# project_team_result.net
KiCad netlist of a schematic drawn in Altium Designer
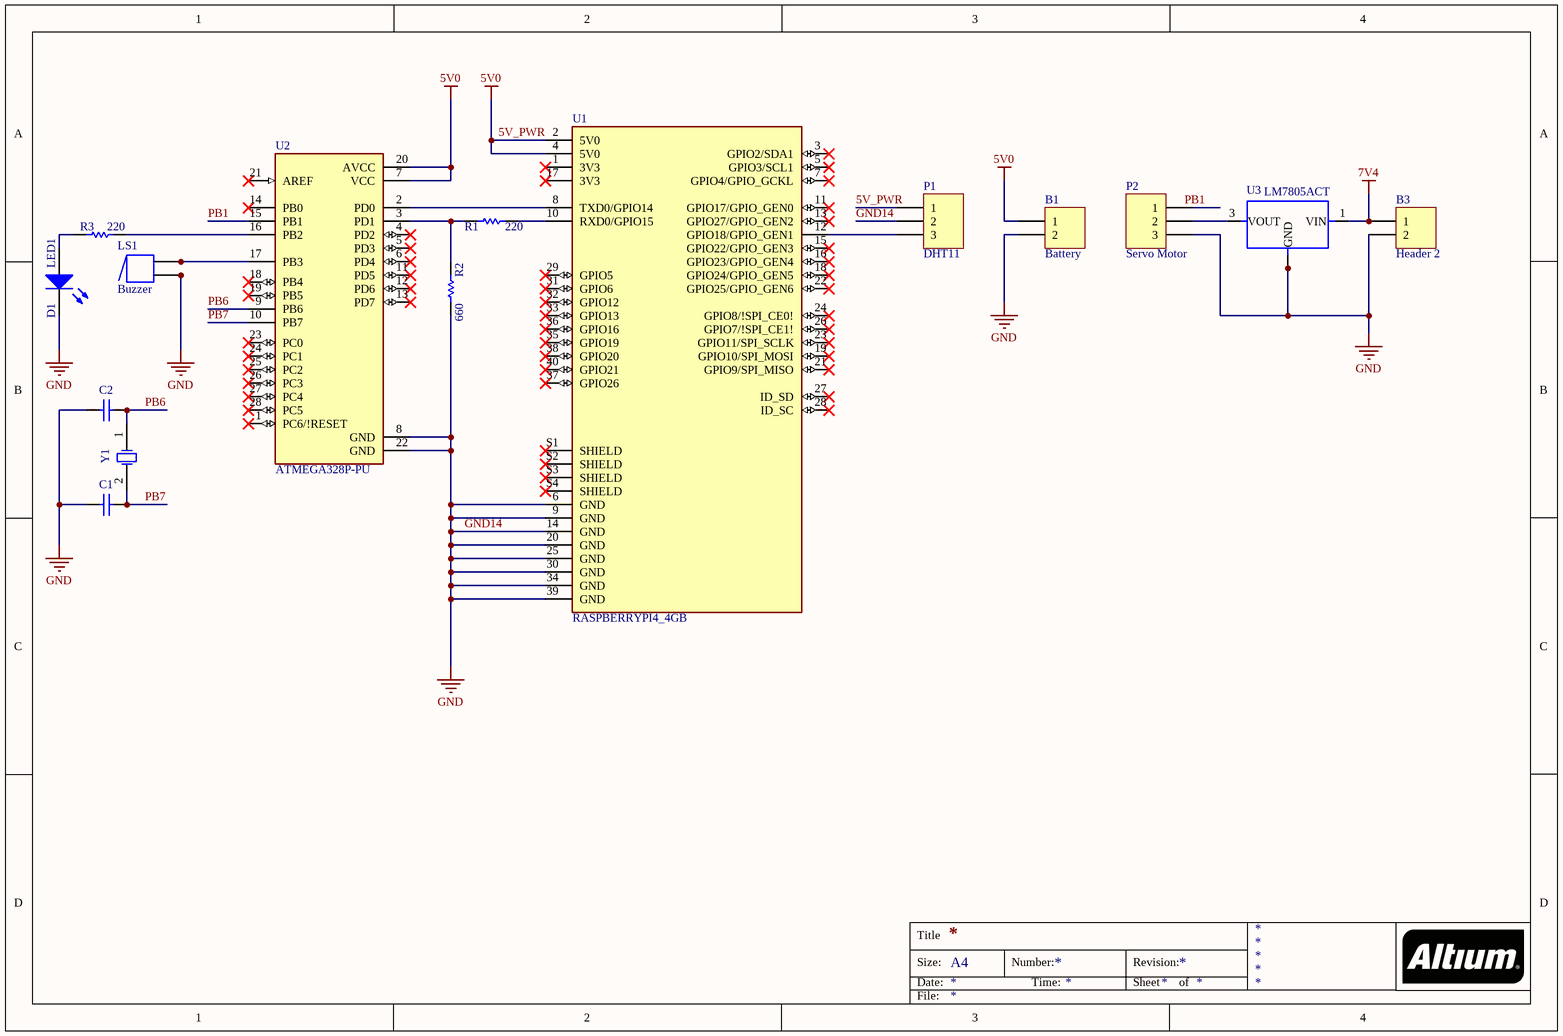
[diagram p0: project_team_result.SchDoc]

(export (version "E")
  (design (tool "Eeschema 10.0.6"))
  (components
    (comp (ref "B1")
      (value "Battery")
      (footprint "HDR1X2")
      (description "Header, 2-Pin")
      (fields (field (name "PUBLISHER") "Altium Limited"))
      (libsource (lib "Miscellaneous Connectors") (part "Header 2"))
    )
    (comp (ref "B3")
      (value "Header 2")
      (footprint "HDR1X2")
      (description "Header, 2-Pin")
      (fields (field (name "PUBLISHER") "Altium Limited"))
      (libsource (lib "Miscellaneous Connectors") (part "Header 2"))
    )
    (comp (ref "C1")
      (value "Cap")
      (footprint "RAD-0.3")
      (description "Capacitor")
      (fields (field (name "PUBLISHER") "Altium Limited"))
      (libsource (lib "Miscellaneous Devices") (part "Cap"))
    )
    (comp (ref "C2")
      (value "Cap")
      (footprint "RAD-0.3")
      (description "Capacitor")
      (fields (field (name "PUBLISHER") "Altium Limited"))
      (libsource (lib "Miscellaneous Devices") (part "Cap"))
    )
    (comp (ref "D1")
      (value "LED1")
      (footprint "LED-1")
      (description "Typical RED GaAs LED")
      (fields (field (name "PUBLISHER") "Altium Limited"))
      (libsource (lib "Miscellaneous Devices") (part "LED1"))
    )
    (comp (ref "LS1")
      (value "Buzzer")
      (footprint "ABSM-1574")
      (description "Magnetic Transducer Buzzer")
      (fields (field (name "PUBLISHER") "Altium Limited"))
      (libsource (lib "Miscellaneous Devices") (part "Buzzer"))
    )
    (comp (ref "P1")
      (value "DHT11")
      (footprint "HDR1X3")
      (description "Header, 3-Pin")
      (fields (field (name "PUBLISHER") "Altium Limited"))
      (libsource (lib "") (part "Header 3_1"))
    )
    (comp (ref "P2")
      (value "Servo Motor")
      (footprint "HDR1X3")
      (description "Header, 3-Pin")
      (fields (field (name "PUBLISHER") "Altium Limited"))
      (libsource (lib "Miscellaneous Connectors") (part "Header 3"))
    )
    (comp (ref "R1")
      (value "220")
      (footprint "AXIAL-0.3")
      (description "Resistor")
      (fields (field (name "Comment") "Res1") (field (name "PUBLISHER") "Altium Limited"))
      (libsource (lib "Miscellaneous Devices") (part "Res1"))
    )
    (comp (ref "R2")
      (value "660")
      (footprint "AXIAL-0.3")
      (description "Resistor")
      (fields (field (name "Comment") "Res1") (field (name "PUBLISHER") "Altium Limited"))
      (libsource (lib "Miscellaneous Devices") (part "Res1"))
    )
    (comp (ref "R3")
      (value "220")
      (footprint "AXIAL-0.3")
      (description "Resistor")
      (fields (field (name "Comment") "Res1") (field (name "PUBLISHER") "Altium Limited"))
      (libsource (lib "Miscellaneous Devices") (part "Res1"))
    )
    (comp (ref "U1")
      (value "RASPBERRYPI4_4GB")
      (footprint "MODULE_RASPBERRYPI4_4GB:MODULE_RASPBERRYPI4_4GB")
      (description "BCM2711 Raspberry Pi 4 Model B 4GB - ARMÂ® CortexÂ®-A72 MPU Embedded Evaluation Board")
      (fields (field (name "MF") "Raspberry Pi Foundation (NF)") (field (name "MP") "RASPBERRYPI4 4GB"))
      (libsource (lib "RASPBERRYPI4_4GB") (part "RASPBERRYPI4_4GB"))
    )
    (comp (ref "U2")
      (value "ATMEGA328P-PU")
      (footprint "SnapEDApcb:DIP794W46P254L2967H457Q28B")
      (description "AVR AVRÂ® ATmega Microcontroller IC 8-Bit 20MHz 32KB _16K x 16_ FLASH 28-PDIP")
      (fields (field (name "MF") "Microchip"))
      (libsource (lib "ATMEGA328P-PU") (part "ATMEGA328P-PU"))
    )
    (comp (ref "U3")
      (value "LM7805ACT")
      (footprint "TO-220")
      (description "Linear Voltage Regulator IC 1 Output 1A TO-220-3")
      (fields (field (name "MF") "ON Semiconductor"))
      (libsource (lib "PMIC-LM7805ACT_TO-220_") (part "PMIC-LM7805ACT(TO-220)"))
    )
    (comp (ref "Y1")
      (value "XTAL")
      (footprint "R38")
      (description "Crystal Oscillator")
      (fields (field (name "PUBLISHER") "Altium Limited"))
      (libsource (lib "Miscellaneous Devices") (part "XTAL"))
    )
  )
  (nets
    (net (code "1") (name "/PB1") (class "Default")
      (node (ref "P2") (pin "1") (pinfunction "1_1") (pintype "passive"))
      (node (ref "U2") (pin "15") (pinfunction "PB1_15") (pintype "passive"))
    )
    (net (code "2") (name "/PB6") (class "Default")
      (node (ref "C2") (pin "2") (pinfunction "2_2") (pintype "passive"))
      (node (ref "U2") (pin "9") (pinfunction "PB6_9") (pintype "passive"))
      (node (ref "Y1") (pin "1") (pinfunction "OSC1_1") (pintype "passive"))
    )
    (net (code "3") (name "/PB7") (class "Default")
      (node (ref "C1") (pin "1") (pinfunction "1_1") (pintype "passive"))
      (node (ref "U2") (pin "10") (pinfunction "PB7_10") (pintype "passive"))
      (node (ref "Y1") (pin "2") (pinfunction "OSC2_2") (pintype "passive"))
    )
    (net (code "4") (name "5V0") (class "Default")
      (node (ref "B1") (pin "1") (pinfunction "1_1") (pintype "passive"))
      (node (ref "P1") (pin "1") (pinfunction "1_1") (pintype "passive"))
      (node (ref "U1") (pin "2") (pinfunction "5V0_2") (pintype "power_in"))
      (node (ref "U1") (pin "4") (pinfunction "5V0_4") (pintype "power_in"))
      (node (ref "U2") (pin "20") (pinfunction "AVCC_20") (pintype "power_in"))
      (node (ref "U2") (pin "7") (pinfunction "VCC_7") (pintype "power_in"))
    )
    (net (code "5") (name "7V4") (class "Default")
      (node (ref "B3") (pin "1") (pinfunction "1_1") (pintype "passive"))
      (node (ref "U3") (pin "1") (pinfunction "VIN_1") (pintype "passive"))
    )
    (net (code "6") (name "GND") (class "Default")
      (node (ref "B1") (pin "2") (pinfunction "2_2") (pintype "passive"))
      (node (ref "B3") (pin "2") (pinfunction "2_2") (pintype "passive"))
      (node (ref "C1") (pin "2") (pinfunction "2_2") (pintype "passive"))
      (node (ref "C2") (pin "1") (pinfunction "1_1") (pintype "passive"))
      (node (ref "D1") (pin "2") (pinfunction "K_2") (pintype "passive"))
      (node (ref "LS1") (pin "2") (pinfunction "2_2") (pintype "passive"))
      (node (ref "LS1") (pin "2A") (pinfunction "2A_2A") (pintype "passive"))
      (node (ref "P1") (pin "2") (pinfunction "2_2") (pintype "passive"))
      (node (ref "P2") (pin "3") (pinfunction "3_3") (pintype "passive"))
      (node (ref "R2") (pin "2") (pinfunction "2_2") (pintype "passive"))
      (node (ref "U1") (pin "14") (pinfunction "GND_14") (pintype "power_in"))
      (node (ref "U1") (pin "20") (pinfunction "GND_20") (pintype "power_in"))
      (node (ref "U1") (pin "25") (pinfunction "GND_25") (pintype "power_in"))
      (node (ref "U1") (pin "30") (pinfunction "GND_30") (pintype "power_in"))
      (node (ref "U1") (pin "34") (pinfunction "GND_34") (pintype "power_in"))
      (node (ref "U1") (pin "39") (pinfunction "GND_39") (pintype "power_in"))
      (node (ref "U1") (pin "6") (pinfunction "GND_6") (pintype "power_in"))
      (node (ref "U1") (pin "9") (pinfunction "GND_9") (pintype "power_in"))
      (node (ref "U2") (pin "22") (pinfunction "GND_22") (pintype "power_in"))
      (node (ref "U2") (pin "8") (pinfunction "GND_8") (pintype "power_in"))
      (node (ref "U3") (pin "2") (pinfunction "GND_2") (pintype "passive"))
      (node (ref "U3") (pin "HEAT") (pinfunction "GND_HEAT") (pintype "passive"))
    )
    (net (code "7") (name "Net-(D1-A)") (class "Default")
      (node (ref "D1") (pin "1") (pinfunction "A_1") (pintype "passive"))
      (node (ref "R3") (pin "1") (pinfunction "1_1") (pintype "passive"))
    )
    (net (code "8") (name "Net-(U1-GPIO18{slash}GPIO_GEN1)") (class "Default")
      (node (ref "P1") (pin "3") (pinfunction "3_3") (pintype "passive"))
      (node (ref "U1") (pin "12") (pinfunction "GPIO18/GPIO_GEN1_12") (pintype "passive"))
    )
    (net (code "9") (name "Net-(U1-RXD0{slash}GPIO15)") (class "Default")
      (node (ref "R1") (pin "2") (pinfunction "2_2") (pintype "passive"))
      (node (ref "U1") (pin "10") (pinfunction "RXD0/GPIO15_10") (pintype "passive"))
    )
    (net (code "10") (name "Net-(U1-TXD0{slash}GPIO14)") (class "Default")
      (node (ref "U1") (pin "8") (pinfunction "TXD0/GPIO14_8") (pintype "passive"))
      (node (ref "U2") (pin "2") (pinfunction "PD0_2") (pintype "passive"))
    )
    (net (code "11") (name "Net-(U2-PB2)") (class "Default")
      (node (ref "R3") (pin "2") (pinfunction "2_2") (pintype "passive"))
      (node (ref "U2") (pin "16") (pinfunction "PB2_16") (pintype "passive"))
    )
    (net (code "12") (name "Net-(U2-PB3)") (class "Default")
      (node (ref "LS1") (pin "1") (pinfunction "1_1") (pintype "passive"))
      (node (ref "LS1") (pin "1A") (pinfunction "1A_1A") (pintype "passive"))
      (node (ref "U2") (pin "17") (pinfunction "PB3_17") (pintype "passive"))
    )
    (net (code "13") (name "Net-(U2-PD1)") (class "Default")
      (node (ref "R1") (pin "1") (pinfunction "1_1") (pintype "passive"))
      (node (ref "R2") (pin "1") (pinfunction "1_1") (pintype "passive"))
      (node (ref "U2") (pin "3") (pinfunction "PD1_3") (pintype "passive"))
    )
    (net (code "14") (name "Net-(U3-VOUT)") (class "Default")
      (node (ref "P2") (pin "2") (pinfunction "2_2") (pintype "passive"))
      (node (ref "U3") (pin "3") (pinfunction "VOUT_3") (pintype "passive"))
    )
    (net (code "15") (name "unconnected-(U1-3V3-Pad1)") (class "Default")
      (node (ref "U1") (pin "1") (pinfunction "3V3_1") (pintype "power_in+no_connect"))
    )
    (net (code "16") (name "unconnected-(U1-3V3-Pad17)") (class "Default")
      (node (ref "U1") (pin "17") (pinfunction "3V3_17") (pintype "power_in+no_connect"))
    )
    (net (code "17") (name "unconnected-(U1-GPIO2{slash}SDA1-Pad3)") (class "Default")
      (node (ref "U1") (pin "3") (pinfunction "GPIO2/SDA1_3") (pintype "bidirectional+no_connect"))
    )
    (net (code "18") (name "unconnected-(U1-GPIO3{slash}SCL1-Pad5)") (class "Default")
      (node (ref "U1") (pin "5") (pinfunction "GPIO3/SCL1_5") (pintype "bidirectional+no_connect"))
    )
    (net (code "19") (name "unconnected-(U1-GPIO4{slash}GPIO_GCKL-Pad7)") (class "Default")
      (node (ref "U1") (pin "7") (pinfunction "GPIO4/GPIO_GCKL_7") (pintype "bidirectional+no_connect"))
    )
    (net (code "20") (name "unconnected-(U1-GPIO5-Pad29)") (class "Default")
      (node (ref "U1") (pin "29") (pinfunction "GPIO5_29") (pintype "bidirectional+no_connect"))
    )
    (net (code "21") (name "unconnected-(U1-GPIO6-Pad31)") (class "Default")
      (node (ref "U1") (pin "31") (pinfunction "GPIO6_31") (pintype "bidirectional+no_connect"))
    )
    (net (code "22") (name "unconnected-(U1-GPIO7{slash}!SPI_CE1!-Pad26)") (class "Default")
      (node (ref "U1") (pin "26") (pinfunction "GPIO7/!SPI_CE1!_26") (pintype "bidirectional+no_connect"))
    )
    (net (code "23") (name "unconnected-(U1-GPIO8{slash}!SPI_CE0!-Pad24)") (class "Default")
      (node (ref "U1") (pin "24") (pinfunction "GPIO8/!SPI_CE0!_24") (pintype "bidirectional+no_connect"))
    )
    (net (code "24") (name "unconnected-(U1-GPIO9{slash}SPI_MISO-Pad21)") (class "Default")
      (node (ref "U1") (pin "21") (pinfunction "GPIO9/SPI_MISO_21") (pintype "bidirectional+no_connect"))
    )
    (net (code "25") (name "unconnected-(U1-GPIO10{slash}SPI_MOSI-Pad19)") (class "Default")
      (node (ref "U1") (pin "19") (pinfunction "GPIO10/SPI_MOSI_19") (pintype "bidirectional+no_connect"))
    )
    (net (code "26") (name "unconnected-(U1-GPIO11{slash}SPI_SCLK-Pad23)") (class "Default")
      (node (ref "U1") (pin "23") (pinfunction "GPIO11/SPI_SCLK_23") (pintype "bidirectional+no_connect"))
    )
    (net (code "27") (name "unconnected-(U1-GPIO12-Pad32)") (class "Default")
      (node (ref "U1") (pin "32") (pinfunction "GPIO12_32") (pintype "bidirectional+no_connect"))
    )
    (net (code "28") (name "unconnected-(U1-GPIO13-Pad33)") (class "Default")
      (node (ref "U1") (pin "33") (pinfunction "GPIO13_33") (pintype "bidirectional+no_connect"))
    )
    (net (code "29") (name "unconnected-(U1-GPIO16-Pad36)") (class "Default")
      (node (ref "U1") (pin "36") (pinfunction "GPIO16_36") (pintype "bidirectional+no_connect"))
    )
    (net (code "30") (name "unconnected-(U1-GPIO17{slash}GPIO_GEN0-Pad11)") (class "Default")
      (node (ref "U1") (pin "11") (pinfunction "GPIO17/GPIO_GEN0_11") (pintype "bidirectional+no_connect"))
    )
    (net (code "31") (name "unconnected-(U1-GPIO19-Pad35)") (class "Default")
      (node (ref "U1") (pin "35") (pinfunction "GPIO19_35") (pintype "bidirectional+no_connect"))
    )
    (net (code "32") (name "unconnected-(U1-GPIO20-Pad38)") (class "Default")
      (node (ref "U1") (pin "38") (pinfunction "GPIO20_38") (pintype "bidirectional+no_connect"))
    )
    (net (code "33") (name "unconnected-(U1-GPIO21-Pad40)") (class "Default")
      (node (ref "U1") (pin "40") (pinfunction "GPIO21_40") (pintype "bidirectional+no_connect"))
    )
    (net (code "34") (name "unconnected-(U1-GPIO22{slash}GPIO_GEN3-Pad15)") (class "Default")
      (node (ref "U1") (pin "15") (pinfunction "GPIO22/GPIO_GEN3_15") (pintype "bidirectional+no_connect"))
    )
    (net (code "35") (name "unconnected-(U1-GPIO23{slash}GPIO_GEN4-Pad16)") (class "Default")
      (node (ref "U1") (pin "16") (pinfunction "GPIO23/GPIO_GEN4_16") (pintype "bidirectional+no_connect"))
    )
    (net (code "36") (name "unconnected-(U1-GPIO24{slash}GPIO_GEN5-Pad18)") (class "Default")
      (node (ref "U1") (pin "18") (pinfunction "GPIO24/GPIO_GEN5_18") (pintype "bidirectional+no_connect"))
    )
    (net (code "37") (name "unconnected-(U1-GPIO25{slash}GPIO_GEN6-Pad22)") (class "Default")
      (node (ref "U1") (pin "22") (pinfunction "GPIO25/GPIO_GEN6_22") (pintype "bidirectional+no_connect"))
    )
    (net (code "38") (name "unconnected-(U1-GPIO26-Pad37)") (class "Default")
      (node (ref "U1") (pin "37") (pinfunction "GPIO26_37") (pintype "bidirectional+no_connect"))
    )
    (net (code "39") (name "unconnected-(U1-GPIO27{slash}GPIO_GEN2-Pad13)") (class "Default")
      (node (ref "U1") (pin "13") (pinfunction "GPIO27/GPIO_GEN2_13") (pintype "bidirectional+no_connect"))
    )
    (net (code "40") (name "unconnected-(U1-ID_SC-Pad28)") (class "Default")
      (node (ref "U1") (pin "28") (pinfunction "ID_SC_28") (pintype "bidirectional+no_connect"))
    )
    (net (code "41") (name "unconnected-(U1-ID_SD-Pad27)") (class "Default")
      (node (ref "U1") (pin "27") (pinfunction "ID_SD_27") (pintype "bidirectional+no_connect"))
    )
    (net (code "42") (name "unconnected-(U1-SHIELD-PadS1)") (class "Default")
      (node (ref "U1") (pin "S1") (pinfunction "SHIELD_S1") (pintype "power_in+no_connect"))
    )
    (net (code "43") (name "unconnected-(U1-SHIELD-PadS2)") (class "Default")
      (node (ref "U1") (pin "S2") (pinfunction "SHIELD_S2") (pintype "power_in+no_connect"))
    )
    (net (code "44") (name "unconnected-(U1-SHIELD-PadS3)") (class "Default")
      (node (ref "U1") (pin "S3") (pinfunction "SHIELD_S3") (pintype "power_in+no_connect"))
    )
    (net (code "45") (name "unconnected-(U1-SHIELD-PadS4)") (class "Default")
      (node (ref "U1") (pin "S4") (pinfunction "SHIELD_S4") (pintype "power_in+no_connect"))
    )
    (net (code "46") (name "unconnected-(U2-AREF-Pad21)") (class "Default")
      (node (ref "U2") (pin "21") (pinfunction "AREF_21") (pintype "input+no_connect"))
    )
    (net (code "47") (name "unconnected-(U2-PB0-Pad14)") (class "Default")
      (node (ref "U2") (pin "14") (pinfunction "PB0_14") (pintype "passive+no_connect"))
    )
    (net (code "48") (name "unconnected-(U2-PB4-Pad18)") (class "Default")
      (node (ref "U2") (pin "18") (pinfunction "PB4_18") (pintype "bidirectional+no_connect"))
    )
    (net (code "49") (name "unconnected-(U2-PB5-Pad19)") (class "Default")
      (node (ref "U2") (pin "19") (pinfunction "PB5_19") (pintype "bidirectional+no_connect"))
    )
    (net (code "50") (name "unconnected-(U2-PC0-Pad23)") (class "Default")
      (node (ref "U2") (pin "23") (pinfunction "PC0_23") (pintype "bidirectional+no_connect"))
    )
    (net (code "51") (name "unconnected-(U2-PC1-Pad24)") (class "Default")
      (node (ref "U2") (pin "24") (pinfunction "PC1_24") (pintype "bidirectional+no_connect"))
    )
    (net (code "52") (name "unconnected-(U2-PC2-Pad25)") (class "Default")
      (node (ref "U2") (pin "25") (pinfunction "PC2_25") (pintype "bidirectional+no_connect"))
    )
    (net (code "53") (name "unconnected-(U2-PC3-Pad26)") (class "Default")
      (node (ref "U2") (pin "26") (pinfunction "PC3_26") (pintype "bidirectional+no_connect"))
    )
    (net (code "54") (name "unconnected-(U2-PC4-Pad27)") (class "Default")
      (node (ref "U2") (pin "27") (pinfunction "PC4_27") (pintype "bidirectional+no_connect"))
    )
    (net (code "55") (name "unconnected-(U2-PC5-Pad28)") (class "Default")
      (node (ref "U2") (pin "28") (pinfunction "PC5_28") (pintype "bidirectional+no_connect"))
    )
    (net (code "56") (name "unconnected-(U2-PC6{slash}!RESET-Pad1)") (class "Default")
      (node (ref "U2") (pin "1") (pinfunction "PC6/!RESET_1") (pintype "bidirectional+no_connect"))
    )
    (net (code "57") (name "unconnected-(U2-PD2-Pad4)") (class "Default")
      (node (ref "U2") (pin "4") (pinfunction "PD2_4") (pintype "bidirectional+no_connect"))
    )
    (net (code "58") (name "unconnected-(U2-PD3-Pad5)") (class "Default")
      (node (ref "U2") (pin "5") (pinfunction "PD3_5") (pintype "bidirectional+no_connect"))
    )
    (net (code "59") (name "unconnected-(U2-PD4-Pad6)") (class "Default")
      (node (ref "U2") (pin "6") (pinfunction "PD4_6") (pintype "bidirectional+no_connect"))
    )
    (net (code "60") (name "unconnected-(U2-PD5-Pad11)") (class "Default")
      (node (ref "U2") (pin "11") (pinfunction "PD5_11") (pintype "bidirectional+no_connect"))
    )
    (net (code "61") (name "unconnected-(U2-PD6-Pad12)") (class "Default")
      (node (ref "U2") (pin "12") (pinfunction "PD6_12") (pintype "bidirectional+no_connect"))
    )
    (net (code "62") (name "unconnected-(U2-PD7-Pad13)") (class "Default")
      (node (ref "U2") (pin "13") (pinfunction "PD7_13") (pintype "bidirectional+no_connect"))
    )
  )
)
